# lumped-transmission-line.net
KiCad netlist of a schematic drawn in EAGLE
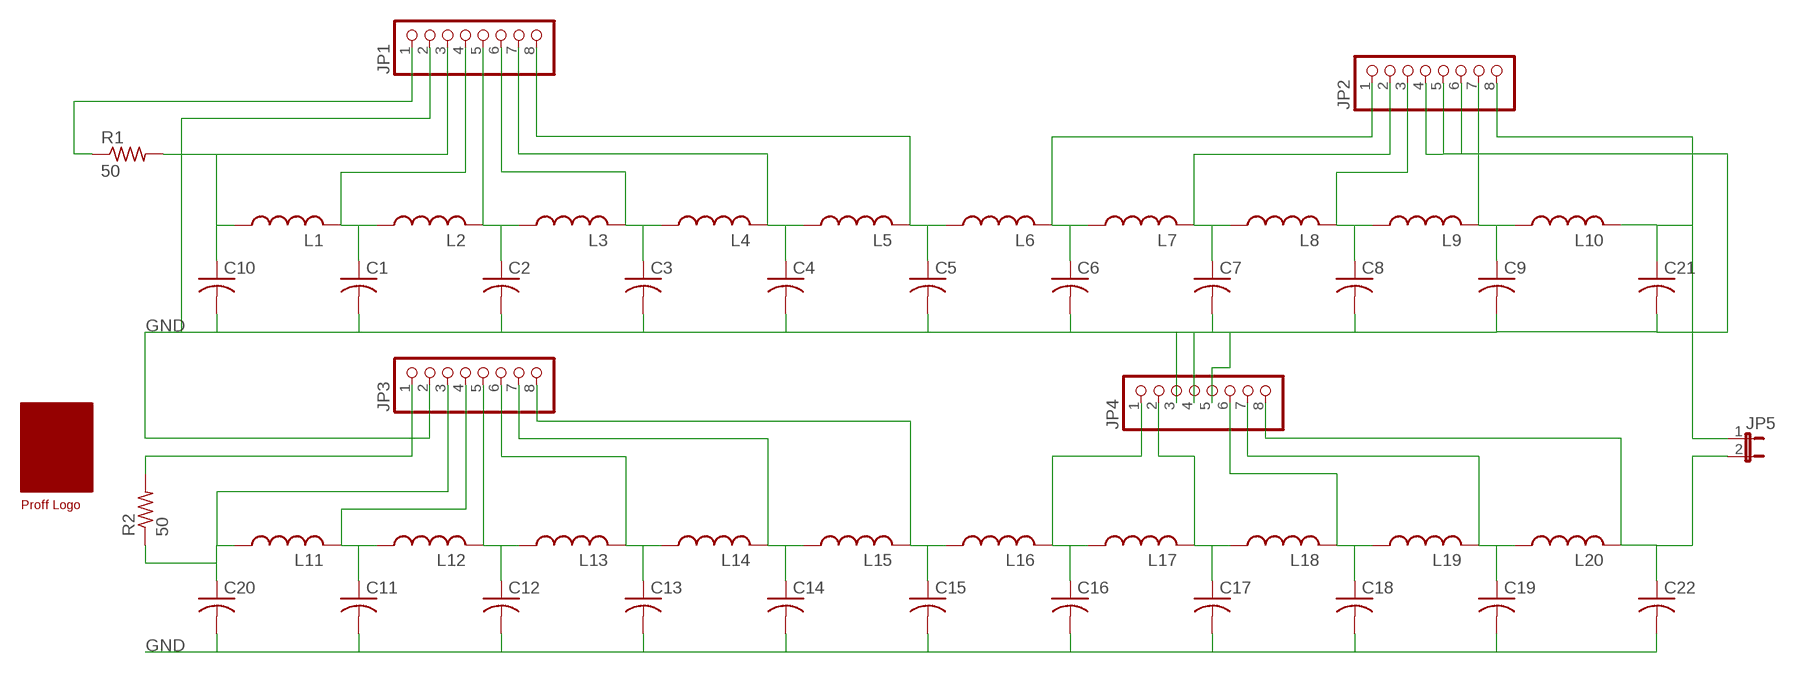
[diagram p0: schematic, sheet 1]

(export (version "E")
  (design (tool "Eeschema 10.0.6"))
  (components
    (comp (ref "C1")
      (value "C-USC1206")
      (footprint "eagle-import:C1206")
      (libsource (lib "eagle-import") (part "C-USC1206"))
    )
    (comp (ref "C2")
      (value "C-USC1206")
      (footprint "eagle-import:C1206")
      (libsource (lib "eagle-import") (part "C-USC1206"))
    )
    (comp (ref "C3")
      (value "C-USC1206")
      (footprint "eagle-import:C1206")
      (libsource (lib "eagle-import") (part "C-USC1206"))
    )
    (comp (ref "C4")
      (value "C-USC1206")
      (footprint "eagle-import:C1206")
      (libsource (lib "eagle-import") (part "C-USC1206"))
    )
    (comp (ref "C5")
      (value "C-USC1206")
      (footprint "eagle-import:C1206")
      (libsource (lib "eagle-import") (part "C-USC1206"))
    )
    (comp (ref "C6")
      (value "C-USC1206")
      (footprint "eagle-import:C1206")
      (libsource (lib "eagle-import") (part "C-USC1206"))
    )
    (comp (ref "C7")
      (value "C-USC1206")
      (footprint "eagle-import:C1206")
      (libsource (lib "eagle-import") (part "C-USC1206"))
    )
    (comp (ref "C8")
      (value "C-USC1206")
      (footprint "eagle-import:C1206")
      (libsource (lib "eagle-import") (part "C-USC1206"))
    )
    (comp (ref "C9")
      (value "C-USC1206")
      (footprint "eagle-import:C1206")
      (libsource (lib "eagle-import") (part "C-USC1206"))
    )
    (comp (ref "C10")
      (value "C-USC1206")
      (footprint "eagle-import:C1206")
      (libsource (lib "eagle-import") (part "C-USC1206"))
    )
    (comp (ref "C11")
      (value "C-USC1206")
      (footprint "eagle-import:C1206")
      (libsource (lib "eagle-import") (part "C-USC1206"))
    )
    (comp (ref "C12")
      (value "C-USC1206")
      (footprint "eagle-import:C1206")
      (libsource (lib "eagle-import") (part "C-USC1206"))
    )
    (comp (ref "C13")
      (value "C-USC1206")
      (footprint "eagle-import:C1206")
      (libsource (lib "eagle-import") (part "C-USC1206"))
    )
    (comp (ref "C14")
      (value "C-USC1206")
      (footprint "eagle-import:C1206")
      (libsource (lib "eagle-import") (part "C-USC1206"))
    )
    (comp (ref "C15")
      (value "C-USC1206")
      (footprint "eagle-import:C1206")
      (libsource (lib "eagle-import") (part "C-USC1206"))
    )
    (comp (ref "C16")
      (value "C-USC1206")
      (footprint "eagle-import:C1206")
      (libsource (lib "eagle-import") (part "C-USC1206"))
    )
    (comp (ref "C17")
      (value "C-USC1206")
      (footprint "eagle-import:C1206")
      (libsource (lib "eagle-import") (part "C-USC1206"))
    )
    (comp (ref "C18")
      (value "C-USC1206")
      (footprint "eagle-import:C1206")
      (libsource (lib "eagle-import") (part "C-USC1206"))
    )
    (comp (ref "C19")
      (value "C-USC1206")
      (footprint "eagle-import:C1206")
      (libsource (lib "eagle-import") (part "C-USC1206"))
    )
    (comp (ref "C20")
      (value "C-USC1206")
      (footprint "eagle-import:C1206")
      (libsource (lib "eagle-import") (part "C-USC1206"))
    )
    (comp (ref "C21")
      (value "C-USC1206")
      (footprint "eagle-import:C1206")
      (libsource (lib "eagle-import") (part "C-USC1206"))
    )
    (comp (ref "C22")
      (value "C-USC1206")
      (footprint "eagle-import:C1206")
      (libsource (lib "eagle-import") (part "C-USC1206"))
    )
    (comp (ref "JP1")
      (value "PINHD-1X8")
      (footprint "eagle-import:1X08")
      (libsource (lib "eagle-import") (part "PINHD-1X8"))
    )
    (comp (ref "JP2")
      (value "PINHD-1X8")
      (footprint "eagle-import:1X08")
      (libsource (lib "eagle-import") (part "PINHD-1X8"))
    )
    (comp (ref "JP3")
      (value "PINHD-1X8")
      (footprint "eagle-import:1X08")
      (libsource (lib "eagle-import") (part "PINHD-1X8"))
    )
    (comp (ref "JP4")
      (value "PINHD-1X8")
      (footprint "eagle-import:1X08")
      (libsource (lib "eagle-import") (part "PINHD-1X8"))
    )
    (comp (ref "JP5")
      (value "JP1E")
      (footprint "eagle-import:JP1")
      (libsource (lib "eagle-import") (part "JP1E"))
    )
    (comp (ref "L1")
      (value "L-USL5650M")
      (footprint "eagle-import:L5650M")
      (libsource (lib "eagle-import") (part "L-USL5650M"))
    )
    (comp (ref "L2")
      (value "L-USL5650M")
      (footprint "eagle-import:L5650M")
      (libsource (lib "eagle-import") (part "L-USL5650M"))
    )
    (comp (ref "L3")
      (value "L-USL5650M")
      (footprint "eagle-import:L5650M")
      (libsource (lib "eagle-import") (part "L-USL5650M"))
    )
    (comp (ref "L4")
      (value "L-USL5650M")
      (footprint "eagle-import:L5650M")
      (libsource (lib "eagle-import") (part "L-USL5650M"))
    )
    (comp (ref "L5")
      (value "L-USL5650M")
      (footprint "eagle-import:L5650M")
      (libsource (lib "eagle-import") (part "L-USL5650M"))
    )
    (comp (ref "L6")
      (value "L-USL5650M")
      (footprint "eagle-import:L5650M")
      (libsource (lib "eagle-import") (part "L-USL5650M"))
    )
    (comp (ref "L7")
      (value "L-USL5650M")
      (footprint "eagle-import:L5650M")
      (libsource (lib "eagle-import") (part "L-USL5650M"))
    )
    (comp (ref "L8")
      (value "L-USL5650M")
      (footprint "eagle-import:L5650M")
      (libsource (lib "eagle-import") (part "L-USL5650M"))
    )
    (comp (ref "L9")
      (value "L-USL5650M")
      (footprint "eagle-import:L5650M")
      (libsource (lib "eagle-import") (part "L-USL5650M"))
    )
    (comp (ref "L10")
      (value "L-USL5650M")
      (footprint "eagle-import:L5650M")
      (libsource (lib "eagle-import") (part "L-USL5650M"))
    )
    (comp (ref "L11")
      (value "L-USL5650M")
      (footprint "eagle-import:L5650M")
      (libsource (lib "eagle-import") (part "L-USL5650M"))
    )
    (comp (ref "L12")
      (value "L-USL5650M")
      (footprint "eagle-import:L5650M")
      (libsource (lib "eagle-import") (part "L-USL5650M"))
    )
    (comp (ref "L13")
      (value "L-USL5650M")
      (footprint "eagle-import:L5650M")
      (libsource (lib "eagle-import") (part "L-USL5650M"))
    )
    (comp (ref "L14")
      (value "L-USL5650M")
      (footprint "eagle-import:L5650M")
      (libsource (lib "eagle-import") (part "L-USL5650M"))
    )
    (comp (ref "L15")
      (value "L-USL5650M")
      (footprint "eagle-import:L5650M")
      (libsource (lib "eagle-import") (part "L-USL5650M"))
    )
    (comp (ref "L16")
      (value "L-USL5650M")
      (footprint "eagle-import:L5650M")
      (libsource (lib "eagle-import") (part "L-USL5650M"))
    )
    (comp (ref "L17")
      (value "L-USL5650M")
      (footprint "eagle-import:L5650M")
      (libsource (lib "eagle-import") (part "L-USL5650M"))
    )
    (comp (ref "L18")
      (value "L-USL5650M")
      (footprint "eagle-import:L5650M")
      (libsource (lib "eagle-import") (part "L-USL5650M"))
    )
    (comp (ref "L19")
      (value "L-USL5650M")
      (footprint "eagle-import:L5650M")
      (libsource (lib "eagle-import") (part "L-USL5650M"))
    )
    (comp (ref "L20")
      (value "L-USL5650M")
      (footprint "eagle-import:L5650M")
      (libsource (lib "eagle-import") (part "L-USL5650M"))
    )
    (comp (ref "R1")
      (value "50")
      (footprint "eagle-import:0204_7")
      (libsource (lib "eagle-import") (part "R-US_0204/7"))
    )
    (comp (ref "R2")
      (value "50")
      (footprint "eagle-import:0204_7")
      (libsource (lib "eagle-import") (part "R-US_0204/7"))
    )
    (comp (ref "U$1")
      (value "PROFF")
      (footprint "eagle-import:PROFF")
      (libsource (lib "eagle-import") (part "PROFF"))
    )
  )
  (nets
    (net (code "1") (name "/GND") (class "Default")
      (node (ref "C1") (pin "2") (pinfunction "2_2") (pintype "passive"))
      (node (ref "C10") (pin "2") (pinfunction "2_2") (pintype "passive"))
      (node (ref "C11") (pin "2") (pinfunction "2_2") (pintype "passive"))
      (node (ref "C12") (pin "2") (pinfunction "2_2") (pintype "passive"))
      (node (ref "C13") (pin "2") (pinfunction "2_2") (pintype "passive"))
      (node (ref "C14") (pin "2") (pinfunction "2_2") (pintype "passive"))
      (node (ref "C15") (pin "2") (pinfunction "2_2") (pintype "passive"))
      (node (ref "C16") (pin "2") (pinfunction "2_2") (pintype "passive"))
      (node (ref "C17") (pin "2") (pinfunction "2_2") (pintype "passive"))
      (node (ref "C18") (pin "2") (pinfunction "2_2") (pintype "passive"))
      (node (ref "C19") (pin "2") (pinfunction "2_2") (pintype "passive"))
      (node (ref "C2") (pin "2") (pinfunction "2_2") (pintype "passive"))
      (node (ref "C20") (pin "2") (pinfunction "2_2") (pintype "passive"))
      (node (ref "C21") (pin "2") (pinfunction "2_2") (pintype "passive"))
      (node (ref "C22") (pin "2") (pinfunction "2_2") (pintype "passive"))
      (node (ref "C3") (pin "2") (pinfunction "2_2") (pintype "passive"))
      (node (ref "C4") (pin "2") (pinfunction "2_2") (pintype "passive"))
      (node (ref "C5") (pin "2") (pinfunction "2_2") (pintype "passive"))
      (node (ref "C6") (pin "2") (pinfunction "2_2") (pintype "passive"))
      (node (ref "C7") (pin "2") (pinfunction "2_2") (pintype "passive"))
      (node (ref "C8") (pin "2") (pinfunction "2_2") (pintype "passive"))
      (node (ref "C9") (pin "2") (pinfunction "2_2") (pintype "passive"))
      (node (ref "JP1") (pin "2") (pinfunction "2_2") (pintype "passive"))
      (node (ref "JP2") (pin "4") (pinfunction "4_4") (pintype "passive"))
      (node (ref "JP2") (pin "5") (pinfunction "5_5") (pintype "passive"))
      (node (ref "JP2") (pin "6") (pinfunction "6_6") (pintype "passive"))
      (node (ref "JP3") (pin "2") (pinfunction "2_2") (pintype "passive"))
      (node (ref "JP4") (pin "3") (pinfunction "3_3") (pintype "passive"))
      (node (ref "JP4") (pin "4") (pinfunction "4_4") (pintype "passive"))
      (node (ref "JP4") (pin "5") (pinfunction "5_5") (pintype "passive"))
    )
    (net (code "2") (name "Net-(C1-Pad1)") (class "Default")
      (node (ref "C1") (pin "1") (pinfunction "1_1") (pintype "passive"))
      (node (ref "JP1") (pin "4") (pinfunction "4_4") (pintype "passive"))
      (node (ref "L1") (pin "2") (pinfunction "2_2") (pintype "passive"))
      (node (ref "L2") (pin "1") (pinfunction "1_1") (pintype "passive"))
    )
    (net (code "3") (name "Net-(C2-Pad1)") (class "Default")
      (node (ref "C2") (pin "1") (pinfunction "1_1") (pintype "passive"))
      (node (ref "JP1") (pin "5") (pinfunction "5_5") (pintype "passive"))
      (node (ref "L2") (pin "2") (pinfunction "2_2") (pintype "passive"))
      (node (ref "L3") (pin "1") (pinfunction "1_1") (pintype "passive"))
    )
    (net (code "4") (name "Net-(C3-Pad1)") (class "Default")
      (node (ref "C3") (pin "1") (pinfunction "1_1") (pintype "passive"))
      (node (ref "JP1") (pin "6") (pinfunction "6_6") (pintype "passive"))
      (node (ref "L3") (pin "2") (pinfunction "2_2") (pintype "passive"))
      (node (ref "L4") (pin "1") (pinfunction "1_1") (pintype "passive"))
    )
    (net (code "5") (name "Net-(C4-Pad1)") (class "Default")
      (node (ref "C4") (pin "1") (pinfunction "1_1") (pintype "passive"))
      (node (ref "JP1") (pin "7") (pinfunction "7_7") (pintype "passive"))
      (node (ref "L4") (pin "2") (pinfunction "2_2") (pintype "passive"))
      (node (ref "L5") (pin "1") (pinfunction "1_1") (pintype "passive"))
    )
    (net (code "6") (name "Net-(C5-Pad1)") (class "Default")
      (node (ref "C5") (pin "1") (pinfunction "1_1") (pintype "passive"))
      (node (ref "JP1") (pin "8") (pinfunction "8_8") (pintype "passive"))
      (node (ref "L5") (pin "2") (pinfunction "2_2") (pintype "passive"))
      (node (ref "L6") (pin "1") (pinfunction "1_1") (pintype "passive"))
    )
    (net (code "7") (name "Net-(C6-Pad1)") (class "Default")
      (node (ref "C6") (pin "1") (pinfunction "1_1") (pintype "passive"))
      (node (ref "JP2") (pin "1") (pinfunction "1_1") (pintype "passive"))
      (node (ref "L6") (pin "2") (pinfunction "2_2") (pintype "passive"))
      (node (ref "L7") (pin "1") (pinfunction "1_1") (pintype "passive"))
    )
    (net (code "8") (name "Net-(C7-Pad1)") (class "Default")
      (node (ref "C7") (pin "1") (pinfunction "1_1") (pintype "passive"))
      (node (ref "JP2") (pin "2") (pinfunction "2_2") (pintype "passive"))
      (node (ref "L7") (pin "2") (pinfunction "2_2") (pintype "passive"))
      (node (ref "L8") (pin "1") (pinfunction "1_1") (pintype "passive"))
    )
    (net (code "9") (name "Net-(C8-Pad1)") (class "Default")
      (node (ref "C8") (pin "1") (pinfunction "1_1") (pintype "passive"))
      (node (ref "JP2") (pin "3") (pinfunction "3_3") (pintype "passive"))
      (node (ref "L8") (pin "2") (pinfunction "2_2") (pintype "passive"))
      (node (ref "L9") (pin "1") (pinfunction "1_1") (pintype "passive"))
    )
    (net (code "10") (name "Net-(C9-Pad1)") (class "Default")
      (node (ref "C9") (pin "1") (pinfunction "1_1") (pintype "passive"))
      (node (ref "JP2") (pin "7") (pinfunction "7_7") (pintype "passive"))
      (node (ref "L10") (pin "1") (pinfunction "1_1") (pintype "passive"))
      (node (ref "L9") (pin "2") (pinfunction "2_2") (pintype "passive"))
    )
    (net (code "11") (name "Net-(C10-Pad1)") (class "Default")
      (node (ref "C10") (pin "1") (pinfunction "1_1") (pintype "passive"))
      (node (ref "JP1") (pin "3") (pinfunction "3_3") (pintype "passive"))
      (node (ref "L1") (pin "1") (pinfunction "1_1") (pintype "passive"))
      (node (ref "R1") (pin "2") (pinfunction "2_2") (pintype "passive"))
    )
    (net (code "12") (name "Net-(C11-Pad1)") (class "Default")
      (node (ref "C11") (pin "1") (pinfunction "1_1") (pintype "passive"))
      (node (ref "JP3") (pin "4") (pinfunction "4_4") (pintype "passive"))
      (node (ref "L11") (pin "2") (pinfunction "2_2") (pintype "passive"))
      (node (ref "L12") (pin "1") (pinfunction "1_1") (pintype "passive"))
    )
    (net (code "13") (name "Net-(C12-Pad1)") (class "Default")
      (node (ref "C12") (pin "1") (pinfunction "1_1") (pintype "passive"))
      (node (ref "JP3") (pin "5") (pinfunction "5_5") (pintype "passive"))
      (node (ref "L12") (pin "2") (pinfunction "2_2") (pintype "passive"))
      (node (ref "L13") (pin "1") (pinfunction "1_1") (pintype "passive"))
    )
    (net (code "14") (name "Net-(C13-Pad1)") (class "Default")
      (node (ref "C13") (pin "1") (pinfunction "1_1") (pintype "passive"))
      (node (ref "JP3") (pin "6") (pinfunction "6_6") (pintype "passive"))
      (node (ref "L13") (pin "2") (pinfunction "2_2") (pintype "passive"))
      (node (ref "L14") (pin "1") (pinfunction "1_1") (pintype "passive"))
    )
    (net (code "15") (name "Net-(C14-Pad1)") (class "Default")
      (node (ref "C14") (pin "1") (pinfunction "1_1") (pintype "passive"))
      (node (ref "JP3") (pin "7") (pinfunction "7_7") (pintype "passive"))
      (node (ref "L14") (pin "2") (pinfunction "2_2") (pintype "passive"))
      (node (ref "L15") (pin "1") (pinfunction "1_1") (pintype "passive"))
    )
    (net (code "16") (name "Net-(C15-Pad1)") (class "Default")
      (node (ref "C15") (pin "1") (pinfunction "1_1") (pintype "passive"))
      (node (ref "JP3") (pin "8") (pinfunction "8_8") (pintype "passive"))
      (node (ref "L15") (pin "2") (pinfunction "2_2") (pintype "passive"))
      (node (ref "L16") (pin "1") (pinfunction "1_1") (pintype "passive"))
    )
    (net (code "17") (name "Net-(C16-Pad1)") (class "Default")
      (node (ref "C16") (pin "1") (pinfunction "1_1") (pintype "passive"))
      (node (ref "JP4") (pin "1") (pinfunction "1_1") (pintype "passive"))
      (node (ref "L16") (pin "2") (pinfunction "2_2") (pintype "passive"))
      (node (ref "L17") (pin "1") (pinfunction "1_1") (pintype "passive"))
    )
    (net (code "18") (name "Net-(C17-Pad1)") (class "Default")
      (node (ref "C17") (pin "1") (pinfunction "1_1") (pintype "passive"))
      (node (ref "JP4") (pin "2") (pinfunction "2_2") (pintype "passive"))
      (node (ref "L17") (pin "2") (pinfunction "2_2") (pintype "passive"))
      (node (ref "L18") (pin "1") (pinfunction "1_1") (pintype "passive"))
    )
    (net (code "19") (name "Net-(C18-Pad1)") (class "Default")
      (node (ref "C18") (pin "1") (pinfunction "1_1") (pintype "passive"))
      (node (ref "JP4") (pin "6") (pinfunction "6_6") (pintype "passive"))
      (node (ref "L18") (pin "2") (pinfunction "2_2") (pintype "passive"))
      (node (ref "L19") (pin "1") (pinfunction "1_1") (pintype "passive"))
    )
    (net (code "20") (name "Net-(C19-Pad1)") (class "Default")
      (node (ref "C19") (pin "1") (pinfunction "1_1") (pintype "passive"))
      (node (ref "JP4") (pin "7") (pinfunction "7_7") (pintype "passive"))
      (node (ref "L19") (pin "2") (pinfunction "2_2") (pintype "passive"))
      (node (ref "L20") (pin "1") (pinfunction "1_1") (pintype "passive"))
    )
    (net (code "21") (name "Net-(C20-Pad1)") (class "Default")
      (node (ref "C20") (pin "1") (pinfunction "1_1") (pintype "passive"))
      (node (ref "JP3") (pin "3") (pinfunction "3_3") (pintype "passive"))
      (node (ref "L11") (pin "1") (pinfunction "1_1") (pintype "passive"))
      (node (ref "R2") (pin "1") (pinfunction "1_1") (pintype "passive"))
    )
    (net (code "22") (name "Net-(C21-Pad1)") (class "Default")
      (node (ref "C21") (pin "1") (pinfunction "1_1") (pintype "passive"))
      (node (ref "JP2") (pin "8") (pinfunction "8_8") (pintype "passive"))
      (node (ref "JP5") (pin "1") (pinfunction "1_1") (pintype "passive"))
      (node (ref "L10") (pin "2") (pinfunction "2_2") (pintype "passive"))
    )
    (net (code "23") (name "Net-(C22-Pad1)") (class "Default")
      (node (ref "C22") (pin "1") (pinfunction "1_1") (pintype "passive"))
      (node (ref "JP4") (pin "8") (pinfunction "8_8") (pintype "passive"))
      (node (ref "JP5") (pin "2") (pinfunction "2_2") (pintype "passive"))
      (node (ref "L20") (pin "2") (pinfunction "2_2") (pintype "passive"))
    )
    (net (code "24") (name "Net-(JP1-Pad1)") (class "Default")
      (node (ref "JP1") (pin "1") (pinfunction "1_1") (pintype "passive"))
      (node (ref "R1") (pin "1") (pinfunction "1_1") (pintype "passive"))
    )
    (net (code "25") (name "Net-(JP3-Pad1)") (class "Default")
      (node (ref "JP3") (pin "1") (pinfunction "1_1") (pintype "passive"))
      (node (ref "R2") (pin "2") (pinfunction "2_2") (pintype "passive"))
    )
  )
)
